# ESP32-S3-WROOM.net
KiCad netlist of a schematic drawn in Altium Designer
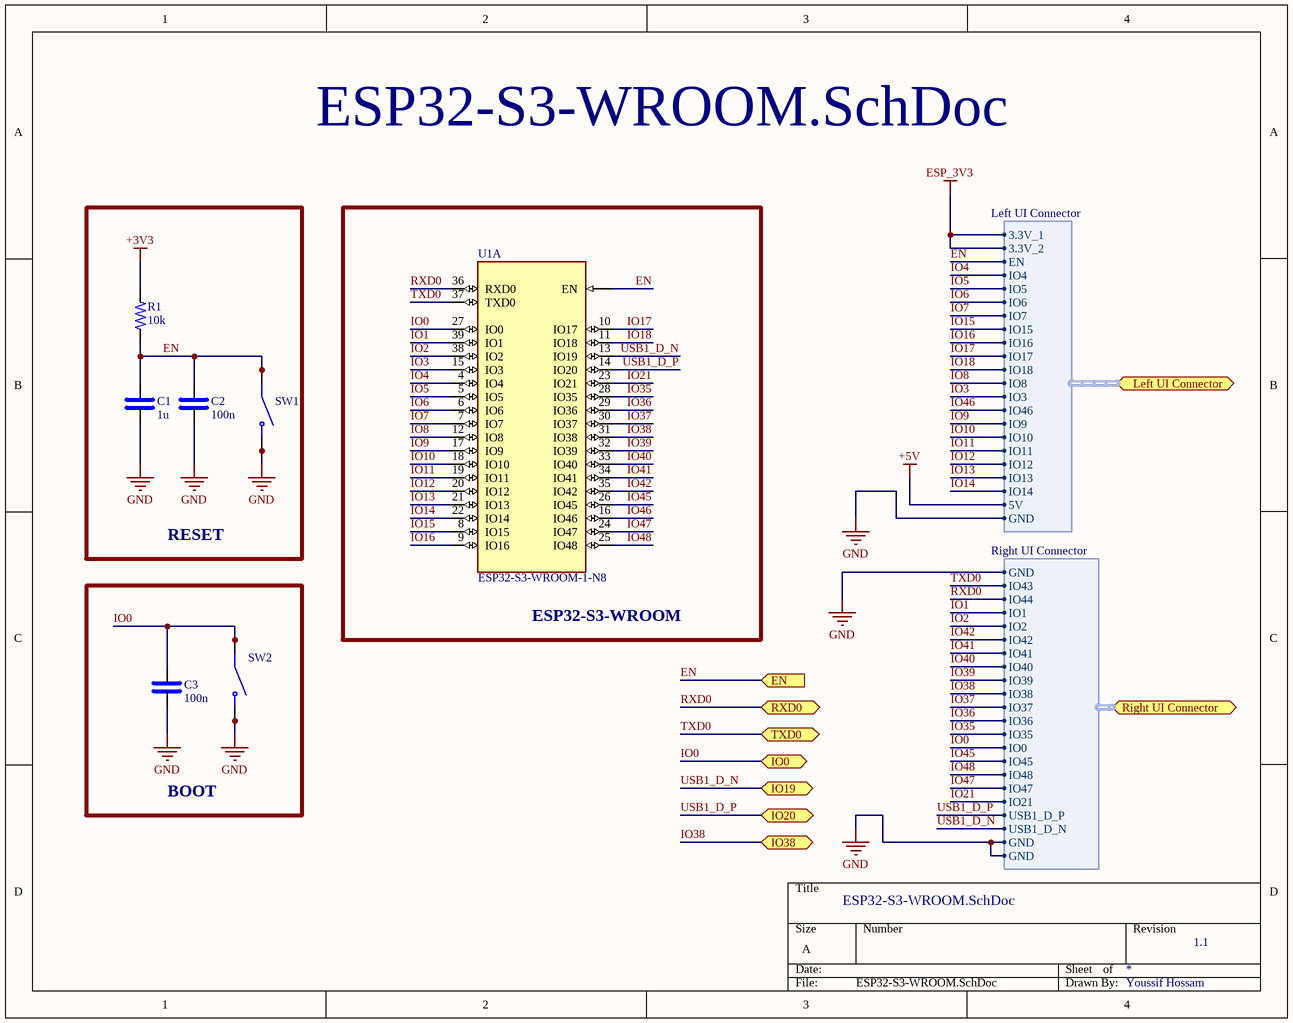
[diagram p0: ESP32-S3-WROOM.SchDoc]

(export (version "E")
  (design (tool "Eeschema 10.0.6"))
  (components
    (comp (ref "C1")
      (value "1u")
      (footprint "FP-GCJ188-0_2-IPC_C")
      (fields
        (field (name "MANUFACTURER") "Murata")
        (field (name "MANUFACTURER PART NUMBER") "GRM188R61E106KA73D")
      )
      (libsource (lib "Integrated_Library") (part "0603 SMD CAP"))
    )
    (comp (ref "C2")
      (value "100n")
      (footprint "0402 CAP")
      (description "Multilayer Ceramic Capacitor, 0.1 uF, 25 V, ï¿½ 10%, X7R, 0402 [1005 Metric]")
      (fields
        (field (name "MANUFACTURER") "Samsung")
        (field (name "MANUFACTURER PART NUMBER") "CL05B104KA5NNNC")
      )
      (libsource (lib "Integrated_Library") (part "0402 SMD Capacitor"))
    )
    (comp (ref "C3")
      (value "100n")
      (footprint "0402 CAP")
      (description "Multilayer Ceramic Capacitor, 0.1 uF, 25 V, ï¿½ 10%, X7R, 0402 [1005 Metric]")
      (fields
        (field (name "MANUFACTURER") "Samsung")
        (field (name "MANUFACTURER PART NUMBER") "CL05B104KA5NNNC")
      )
      (libsource (lib "Integrated_Library") (part "0402 SMD Capacitor"))
    )
    (comp (ref "R1")
      (value "10k")
      (footprint "0402 RES")
      (description "Res Thick Film 0402 10K Ohm 5% 0.125W(1/8W) ±200ppm/C Pad SMD T/R")
      (fields
        (field (name "MANUFACTURER") "Yageo")
        (field (name "MANUFACTURER PART NUMBER") "RC0402JR-7W10KL")
      )
      (libsource (lib "Integrated_Library") (part "0402 SMD Resistor"))
    )
    (comp (ref "SW1")
      (value "KMR731NGLFS")
      (footprint "SW_KMR731NGLFS")
      (description "Tactile Switch SPST-NO Top Actuated Surface Mount")
      (fields (field (name "MF") "C&K"))
      (libsource (lib "Integrated_Library") (part "KMR731NGLFS"))
    )
    (comp (ref "SW2")
      (value "KMR731NGLFS")
      (footprint "SW_KMR731NGLFS")
      (description "Tactile Switch SPST-NO Top Actuated Surface Mount")
      (fields (field (name "MF") "C&K"))
      (libsource (lib "Integrated_Library") (part "KMR731NGLFS"))
    )
    (comp (ref "U1")
      (value "ESP32-S3-WROOM-1-N8")
      (footprint "XCVR_ESP32-S3-WROOM-1-N8")
      (fields (field (name "MF") "{'manufacturer': u'Espressif Systems'}"))
      (libsource (lib "Integrated_Library") (part "ESP32-S3-WROOM-1-N8"))
    )
  )
  (nets
    (net (code "5") (name "+3V3") (class "Default")
      (node (ref "R1") (pin "2") (pinfunction "2_2") (pintype "passive"))
    )
    (net (code "7") (name "/EN") (class "Default")
      (node (ref "C1") (pin "2") (pinfunction "2_2") (pintype "passive"))
      (node (ref "C2") (pin "2") (pinfunction "2_2") (pintype "passive"))
      (node (ref "R1") (pin "1") (pinfunction "1_1") (pintype "passive"))
      (node (ref "SW1") (pin "3") (pinfunction "COM_3") (pintype "passive"))
      (node (ref "SW1") (pin "4") (pinfunction "COM_4") (pintype "passive"))
      (node (ref "U1") (pin "3") (pinfunction "EN_3") (pintype "input"))
    )
    (net (code "8") (name "/IO0") (class "Default")
      (node (ref "C3") (pin "2") (pinfunction "2_2") (pintype "passive"))
      (node (ref "SW2") (pin "3") (pinfunction "COM_3") (pintype "passive"))
      (node (ref "SW2") (pin "4") (pinfunction "COM_4") (pintype "passive"))
      (node (ref "U1") (pin "27") (pinfunction "IO0_27") (pintype "bidirectional"))
    )
    (net (code "9") (name "/IO1") (class "Default")
      (node (ref "U1") (pin "39") (pinfunction "IO1_39") (pintype "bidirectional"))
    )
    (net (code "10") (name "/IO2") (class "Default")
      (node (ref "U1") (pin "38") (pinfunction "IO2_38") (pintype "bidirectional"))
    )
    (net (code "11") (name "/IO3") (class "Default")
      (node (ref "U1") (pin "15") (pinfunction "IO3_15") (pintype "bidirectional"))
    )
    (net (code "12") (name "/IO4") (class "Default")
      (node (ref "U1") (pin "4") (pinfunction "IO4_4") (pintype "bidirectional"))
    )
    (net (code "13") (name "/IO5") (class "Default")
      (node (ref "U1") (pin "5") (pinfunction "IO5_5") (pintype "bidirectional"))
    )
    (net (code "14") (name "/IO6") (class "Default")
      (node (ref "U1") (pin "6") (pinfunction "IO6_6") (pintype "bidirectional"))
    )
    (net (code "15") (name "/IO7") (class "Default")
      (node (ref "U1") (pin "7") (pinfunction "IO7_7") (pintype "bidirectional"))
    )
    (net (code "16") (name "/IO8") (class "Default")
      (node (ref "U1") (pin "12") (pinfunction "IO8_12") (pintype "bidirectional"))
    )
    (net (code "17") (name "/IO9") (class "Default")
      (node (ref "U1") (pin "17") (pinfunction "IO9_17") (pintype "bidirectional"))
    )
    (net (code "18") (name "/IO10") (class "Default")
      (node (ref "U1") (pin "18") (pinfunction "IO10_18") (pintype "bidirectional"))
    )
    (net (code "19") (name "/IO11") (class "Default")
      (node (ref "U1") (pin "19") (pinfunction "IO11_19") (pintype "bidirectional"))
    )
    (net (code "20") (name "/IO12") (class "Default")
      (node (ref "U1") (pin "20") (pinfunction "IO12_20") (pintype "bidirectional"))
    )
    (net (code "21") (name "/IO13") (class "Default")
      (node (ref "U1") (pin "21") (pinfunction "IO13_21") (pintype "bidirectional"))
    )
    (net (code "22") (name "/IO14") (class "Default")
      (node (ref "U1") (pin "22") (pinfunction "IO14_22") (pintype "bidirectional"))
    )
    (net (code "23") (name "/IO15") (class "Default")
      (node (ref "U1") (pin "8") (pinfunction "IO15_8") (pintype "bidirectional"))
    )
    (net (code "24") (name "/IO16") (class "Default")
      (node (ref "U1") (pin "9") (pinfunction "IO16_9") (pintype "bidirectional"))
    )
    (net (code "25") (name "/IO17") (class "Default")
      (node (ref "U1") (pin "10") (pinfunction "IO17_10") (pintype "bidirectional"))
    )
    (net (code "26") (name "/IO18") (class "Default")
      (node (ref "U1") (pin "11") (pinfunction "IO18_11") (pintype "bidirectional"))
    )
    (net (code "27") (name "/IO21") (class "Default")
      (node (ref "U1") (pin "23") (pinfunction "IO21_23") (pintype "bidirectional"))
    )
    (net (code "28") (name "/IO35") (class "Default")
      (node (ref "U1") (pin "28") (pinfunction "IO35_28") (pintype "bidirectional"))
    )
    (net (code "29") (name "/IO36") (class "Default")
      (node (ref "U1") (pin "29") (pinfunction "IO36_29") (pintype "bidirectional"))
    )
    (net (code "30") (name "/IO37") (class "Default")
      (node (ref "U1") (pin "30") (pinfunction "IO37_30") (pintype "bidirectional"))
    )
    (net (code "31") (name "/IO38") (class "Default")
      (node (ref "U1") (pin "31") (pinfunction "IO38_31") (pintype "bidirectional"))
    )
    (net (code "32") (name "/IO39") (class "Default")
      (node (ref "U1") (pin "32") (pinfunction "IO39_32") (pintype "bidirectional"))
    )
    (net (code "33") (name "/IO40") (class "Default")
      (node (ref "U1") (pin "33") (pinfunction "IO40_33") (pintype "bidirectional"))
    )
    (net (code "34") (name "/IO41") (class "Default")
      (node (ref "U1") (pin "34") (pinfunction "IO41_34") (pintype "bidirectional"))
    )
    (net (code "35") (name "/IO42") (class "Default")
      (node (ref "U1") (pin "35") (pinfunction "IO42_35") (pintype "bidirectional"))
    )
    (net (code "36") (name "/IO45") (class "Default")
      (node (ref "U1") (pin "26") (pinfunction "IO45_26") (pintype "bidirectional"))
    )
    (net (code "37") (name "/IO46") (class "Default")
      (node (ref "U1") (pin "16") (pinfunction "IO46_16") (pintype "bidirectional"))
    )
    (net (code "38") (name "/IO47") (class "Default")
      (node (ref "U1") (pin "24") (pinfunction "IO47_24") (pintype "bidirectional"))
    )
    (net (code "39") (name "/IO48") (class "Default")
      (node (ref "U1") (pin "25") (pinfunction "IO48_25") (pintype "bidirectional"))
    )
    (net (code "40") (name "/RXD0") (class "Default")
      (node (ref "U1") (pin "36") (pinfunction "RXD0_36") (pintype "bidirectional"))
    )
    (net (code "41") (name "/TXD0") (class "Default")
      (node (ref "U1") (pin "37") (pinfunction "TXD0_37") (pintype "bidirectional"))
    )
    (net (code "42") (name "/USB1_D_N") (class "Default")
      (node (ref "U1") (pin "13") (pinfunction "IO19_13") (pintype "bidirectional"))
    )
    (net (code "43") (name "/USB1_D_P") (class "Default")
      (node (ref "U1") (pin "14") (pinfunction "IO20_14") (pintype "bidirectional"))
    )
    (net (code "47") (name "GND") (class "Default")
      (node (ref "C1") (pin "1") (pinfunction "1_1") (pintype "passive"))
      (node (ref "C2") (pin "1") (pinfunction "1_1") (pintype "passive"))
      (node (ref "C3") (pin "1") (pinfunction "1_1") (pintype "passive"))
      (node (ref "SW1") (pin "1") (pinfunction "NO_1") (pintype "passive"))
      (node (ref "SW1") (pin "2") (pinfunction "NO_2") (pintype "passive"))
      (node (ref "SW2") (pin "1") (pinfunction "NO_1") (pintype "passive"))
      (node (ref "SW2") (pin "2") (pinfunction "NO_2") (pintype "passive"))
    )
  )
)
